# puente_H_rama_1.net
KiCad netlist of a schematic drawn in Altium Designer
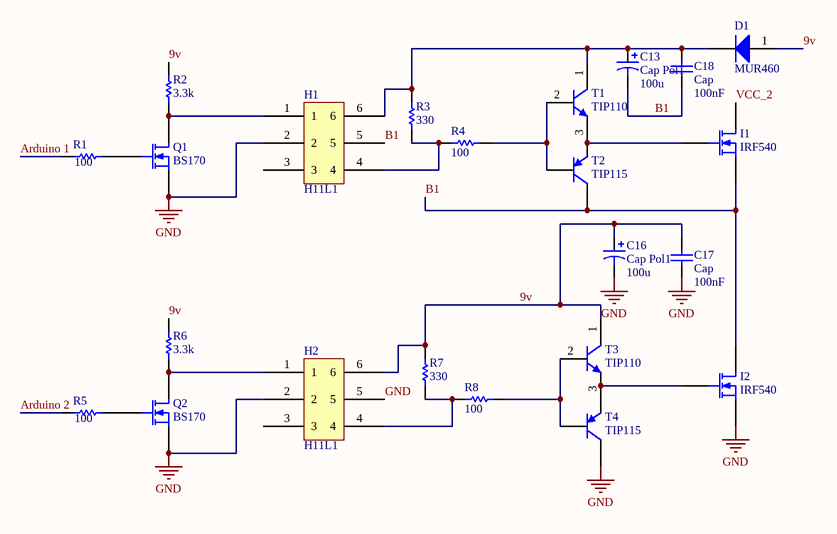
[diagram p0: puente H rama 1.SchDoc]

(export (version "E")
  (design (tool "Eeschema 10.0.6"))
  (components
    (comp (ref "C13")
      (value "Cap Pol1")
      (footprint "A")
      (description "Polarized Capacitor (Radial)")
      (fields (field (name "ALTIUM_VALUE") "100u") (field (name "PUBLISHER") "Altium Limited"))
      (libsource (lib "Miscellaneous Devices") (part "Cap Pol1"))
    )
    (comp (ref "C16")
      (value "Cap Pol1")
      (footprint "A")
      (description "Polarized Capacitor (Radial)")
      (fields (field (name "ALTIUM_VALUE") "100u") (field (name "PUBLISHER") "Altium Limited"))
      (libsource (lib "Miscellaneous Devices") (part "Cap Pol1"))
    )
    (comp (ref "C17")
      (value "Cap")
      (footprint "C1206")
      (description "Capacitor")
      (fields (field (name "ALTIUM_VALUE") "100nF") (field (name "PUBLISHER") "Altium Limited"))
      (libsource (lib "Miscellaneous Devices") (part "Cap"))
    )
    (comp (ref "C18")
      (value "Cap")
      (footprint "C1206")
      (description "Capacitor")
      (fields (field (name "ALTIUM_VALUE") "100nF") (field (name "PUBLISHER") "Altium Limited"))
      (libsource (lib "Miscellaneous Devices") (part "Cap"))
    )
    (comp (ref "D1")
      (value "MUR460")
      (footprint "DO-201AD")
      (description "Default Diode")
      (fields (field (name "PUBLISHER") "Altium Limited"))
      (libsource (lib "Miscellaneous Devices") (part "Diode"))
    )
    (comp (ref "H1") (value "H11L1") (footprint "DIP-6") (libsource (lib "H11L1") (part "H11L1")))
    (comp (ref "H2") (value "H11L1") (footprint "DIP-6") (libsource (lib "H11L1") (part "H11L1")))
    (comp (ref "I1")
      (value "IRF540")
      (footprint "TO-220AB")
      (description "N-Channel MOSFET")
      (fields (field (name "PUBLISHER") "Altium Limited"))
      (libsource (lib "Miscellaneous Devices") (part "MOSFET-N"))
    )
    (comp (ref "I2")
      (value "IRF540")
      (footprint "TO-220-AB")
      (description "N-Channel MOSFET")
      (fields (field (name "PUBLISHER") "Altium Limited"))
      (libsource (lib "Miscellaneous Devices") (part "MOSFET-N"))
    )
    (comp (ref "Q1")
      (value "BS170")
      (footprint "E3")
      (description "N-Channel MOSFET")
      (fields (field (name "PUBLISHER") "Altium Limited"))
      (libsource (lib "Miscellaneous Devices") (part "MOSFET-N"))
    )
    (comp (ref "Q2")
      (value "BS170")
      (footprint "E3")
      (description "N-Channel MOSFET")
      (fields (field (name "PUBLISHER") "Altium Limited"))
      (libsource (lib "Miscellaneous Devices") (part "MOSFET-N"))
    )
    (comp (ref "R1")
      (value "100")
      (footprint "3216[1206]")
      (description "Resistor")
      (fields (field (name "Comment") "Res1") (field (name "PUBLISHER") "Altium Limited"))
      (libsource (lib "Miscellaneous Devices") (part "Res1"))
    )
    (comp (ref "R2")
      (value "3.3k")
      (footprint "3216[1206]")
      (description "Resistor")
      (fields (field (name "Comment") "Res1") (field (name "PUBLISHER") "Altium Limited"))
      (libsource (lib "Miscellaneous Devices") (part "Res1"))
    )
    (comp (ref "R3")
      (value "330")
      (footprint "3216[1206]")
      (description "Resistor")
      (fields (field (name "Comment") "Res1") (field (name "PUBLISHER") "Altium Limited"))
      (libsource (lib "Miscellaneous Devices") (part "Res1"))
    )
    (comp (ref "R4")
      (value "100")
      (footprint "3216[1206]")
      (description "Resistor")
      (fields (field (name "Comment") "Res1") (field (name "PUBLISHER") "Altium Limited"))
      (libsource (lib "Miscellaneous Devices") (part "Res1"))
    )
    (comp (ref "R5")
      (value "100")
      (footprint "3216[1206]")
      (description "Resistor")
      (fields (field (name "Comment") "Res1") (field (name "PUBLISHER") "Altium Limited"))
      (libsource (lib "Miscellaneous Devices") (part "Res1"))
    )
    (comp (ref "R6")
      (value "3.3k")
      (footprint "3216[1206]")
      (description "Resistor")
      (fields (field (name "Comment") "Res1") (field (name "PUBLISHER") "Altium Limited"))
      (libsource (lib "Miscellaneous Devices") (part "Res1"))
    )
    (comp (ref "R7")
      (value "330")
      (footprint "3216[1206]")
      (description "Resistor")
      (fields (field (name "Comment") "Res1") (field (name "PUBLISHER") "Altium Limited"))
      (libsource (lib "Miscellaneous Devices") (part "Res1"))
    )
    (comp (ref "R8")
      (value "100")
      (footprint "3216[1206]")
      (description "Resistor")
      (fields (field (name "Comment") "Res1") (field (name "PUBLISHER") "Altium Limited"))
      (libsource (lib "Miscellaneous Devices") (part "Res1"))
    )
    (comp (ref "T1")
      (value "TIP110")
      (footprint "TO-220-AB")
      (description "NPN Bipolar Transistor")
      (fields (field (name "PUBLISHER") "Altium Limited"))
      (libsource (lib "Miscellaneous Devices") (part "NPN"))
    )
    (comp (ref "T2")
      (value "TIP115")
      (footprint "TO-220-AB")
      (description "PNP Bipolar Transistor")
      (fields (field (name "PUBLISHER") "Altium Limited"))
      (libsource (lib "Miscellaneous Devices") (part "PNP"))
    )
    (comp (ref "T3")
      (value "TIP110")
      (footprint "TO-220-AB")
      (description "NPN Bipolar Transistor")
      (fields (field (name "PUBLISHER") "Altium Limited"))
      (libsource (lib "Miscellaneous Devices") (part "NPN"))
    )
    (comp (ref "T4")
      (value "TIP115")
      (footprint "TO-220-AB")
      (description "PNP Bipolar Transistor")
      (fields (field (name "PUBLISHER") "Altium Limited"))
      (libsource (lib "Miscellaneous Devices") (part "PNP"))
    )
  )
  (nets
    (net (code "1") (name "/9v") (class "Default")
      (node (ref "C16") (pin "1") (pinfunction "1_1") (pintype "passive"))
      (node (ref "C17") (pin "2") (pinfunction "2_2") (pintype "passive"))
      (node (ref "D1") (pin "1") (pinfunction "A_1") (pintype "passive"))
      (node (ref "H2") (pin "6") (pinfunction "6_6") (pintype "passive"))
      (node (ref "R2") (pin "2") (pinfunction "2_2") (pintype "passive"))
      (node (ref "R6") (pin "2") (pinfunction "2_2") (pintype "passive"))
      (node (ref "R7") (pin "2") (pinfunction "2_2") (pintype "passive"))
      (node (ref "T3") (pin "1") (pinfunction "C_1") (pintype "passive"))
    )
    (net (code "2") (name "/Arduino 1") (class "Default")
      (node (ref "R1") (pin "1") (pinfunction "1_1") (pintype "passive"))
    )
    (net (code "3") (name "/Arduino 2") (class "Default")
      (node (ref "R5") (pin "1") (pinfunction "1_1") (pintype "passive"))
    )
    (net (code "4") (name "/B1") (class "Default")
      (node (ref "C13") (pin "2") (pinfunction "2_2") (pintype "passive"))
      (node (ref "C18") (pin "1") (pinfunction "1_1") (pintype "passive"))
      (node (ref "H1") (pin "5") (pinfunction "5_5") (pintype "passive"))
      (node (ref "I1") (pin "3") (pinfunction "S_3") (pintype "passive"))
      (node (ref "I2") (pin "1") (pinfunction "D_1") (pintype "passive"))
      (node (ref "T2") (pin "1") (pinfunction "C_1") (pintype "passive"))
    )
    (net (code "5") (name "/VCC_2") (class "Default")
      (node (ref "I1") (pin "1") (pinfunction "D_1") (pintype "passive"))
    )
    (net (code "6") (name "GND") (class "Default")
      (node (ref "C16") (pin "2") (pinfunction "2_2") (pintype "passive"))
      (node (ref "C17") (pin "1") (pinfunction "1_1") (pintype "passive"))
      (node (ref "H1") (pin "2") (pinfunction "2_2") (pintype "passive"))
      (node (ref "H2") (pin "2") (pinfunction "2_2") (pintype "passive"))
      (node (ref "H2") (pin "5") (pinfunction "5_5") (pintype "passive"))
      (node (ref "I2") (pin "3") (pinfunction "S_3") (pintype "passive"))
      (node (ref "Q1") (pin "3") (pinfunction "S_3") (pintype "passive"))
      (node (ref "Q2") (pin "3") (pinfunction "S_3") (pintype "passive"))
      (node (ref "T4") (pin "1") (pinfunction "C_1") (pintype "passive"))
    )
    (net (code "7") (name "Net-(D1-K)") (class "Default")
      (node (ref "C13") (pin "1") (pinfunction "1_1") (pintype "passive"))
      (node (ref "C18") (pin "2") (pinfunction "2_2") (pintype "passive"))
      (node (ref "D1") (pin "2") (pinfunction "K_2") (pintype "passive"))
      (node (ref "H1") (pin "6") (pinfunction "6_6") (pintype "passive"))
      (node (ref "R3") (pin "2") (pinfunction "2_2") (pintype "passive"))
      (node (ref "T1") (pin "1") (pinfunction "C_1") (pintype "passive"))
    )
    (net (code "8") (name "Net-(H1-Pad4)") (class "Default")
      (node (ref "H1") (pin "4") (pinfunction "4_4") (pintype "passive"))
      (node (ref "R3") (pin "1") (pinfunction "1_1") (pintype "passive"))
      (node (ref "R4") (pin "2") (pinfunction "2_2") (pintype "passive"))
    )
    (net (code "9") (name "Net-(H2-Pad4)") (class "Default")
      (node (ref "H2") (pin "4") (pinfunction "4_4") (pintype "passive"))
      (node (ref "R7") (pin "1") (pinfunction "1_1") (pintype "passive"))
      (node (ref "R8") (pin "2") (pinfunction "2_2") (pintype "passive"))
    )
    (net (code "10") (name "Net-(I1-G)") (class "Default")
      (node (ref "I1") (pin "2") (pinfunction "G_2") (pintype "passive"))
      (node (ref "T1") (pin "3") (pinfunction "E_3") (pintype "passive"))
      (node (ref "T2") (pin "3") (pinfunction "E_3") (pintype "passive"))
    )
    (net (code "11") (name "Net-(I2-G)") (class "Default")
      (node (ref "I2") (pin "2") (pinfunction "G_2") (pintype "passive"))
      (node (ref "T3") (pin "3") (pinfunction "E_3") (pintype "passive"))
      (node (ref "T4") (pin "3") (pinfunction "E_3") (pintype "passive"))
    )
    (net (code "12") (name "Net-(Q1-D)") (class "Default")
      (node (ref "H1") (pin "1") (pinfunction "1_1") (pintype "passive"))
      (node (ref "Q1") (pin "1") (pinfunction "D_1") (pintype "passive"))
      (node (ref "R2") (pin "1") (pinfunction "1_1") (pintype "passive"))
    )
    (net (code "13") (name "Net-(Q1-G)") (class "Default")
      (node (ref "Q1") (pin "2") (pinfunction "G_2") (pintype "passive"))
      (node (ref "R1") (pin "2") (pinfunction "2_2") (pintype "passive"))
    )
    (net (code "14") (name "Net-(Q2-D)") (class "Default")
      (node (ref "H2") (pin "1") (pinfunction "1_1") (pintype "passive"))
      (node (ref "Q2") (pin "1") (pinfunction "D_1") (pintype "passive"))
      (node (ref "R6") (pin "1") (pinfunction "1_1") (pintype "passive"))
    )
    (net (code "15") (name "Net-(Q2-G)") (class "Default")
      (node (ref "Q2") (pin "2") (pinfunction "G_2") (pintype "passive"))
      (node (ref "R5") (pin "2") (pinfunction "2_2") (pintype "passive"))
    )
    (net (code "16") (name "Net-(T1-B)") (class "Default")
      (node (ref "R4") (pin "1") (pinfunction "1_1") (pintype "passive"))
      (node (ref "T1") (pin "2") (pinfunction "B_2") (pintype "passive"))
      (node (ref "T2") (pin "2") (pinfunction "B_2") (pintype "passive"))
    )
    (net (code "17") (name "Net-(T3-B)") (class "Default")
      (node (ref "R8") (pin "1") (pinfunction "1_1") (pintype "passive"))
      (node (ref "T3") (pin "2") (pinfunction "B_2") (pintype "passive"))
      (node (ref "T4") (pin "2") (pinfunction "B_2") (pintype "passive"))
    )
    (net (code "18") (name "unconnected-(H1-Pad3)") (class "Default")
      (node (ref "H1") (pin "3") (pinfunction "3_3") (pintype "passive"))
    )
    (net (code "19") (name "unconnected-(H2-Pad3)") (class "Default")
      (node (ref "H2") (pin "3") (pinfunction "3_3") (pintype "passive"))
    )
  )
)
